# mcu.net
KiCad netlist of a schematic drawn in Altium Designer
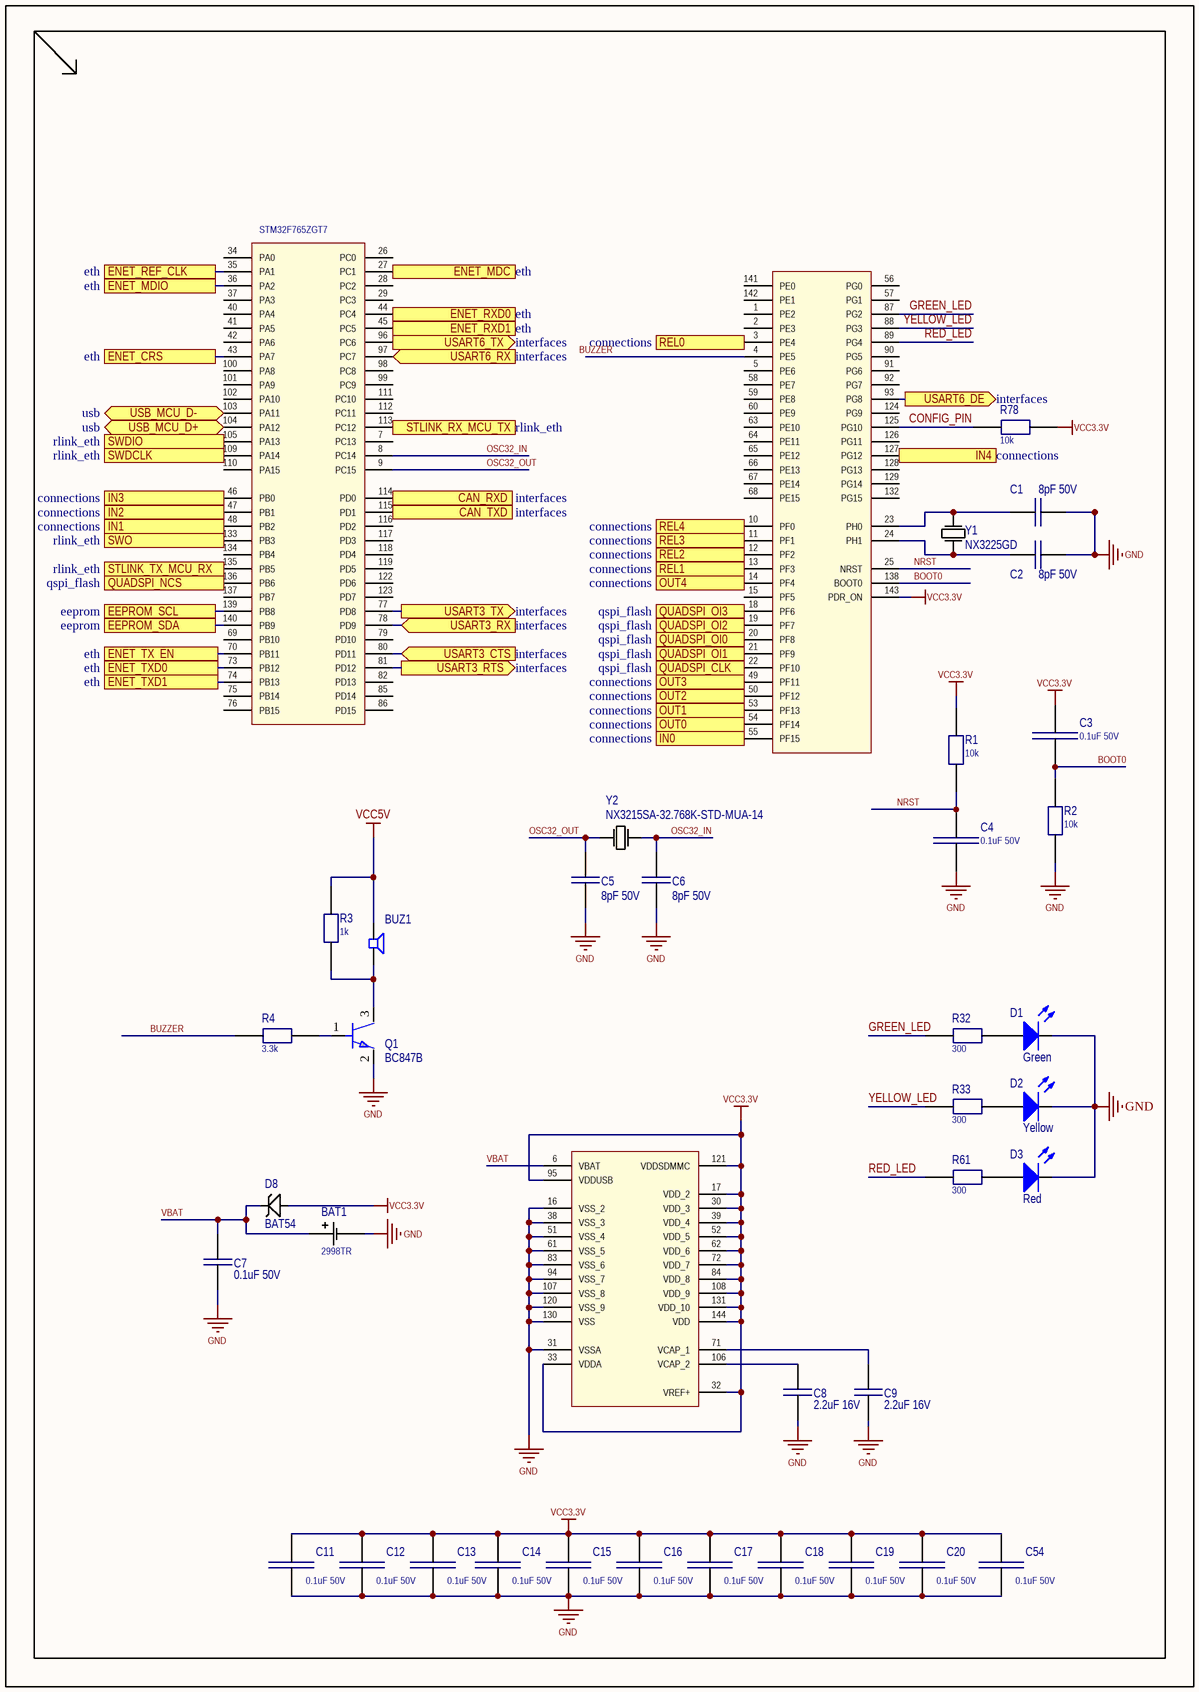
[diagram p0: mcu.SchDoc]

(export (version "E")
  (design (tool "Eeschema 10.0.6"))
  (components
    (comp (ref "BAT1")
      (value "2998TR")
      (footprint "BAT_2998TR")
      (description "Battery")
      (libsource (lib "battery_socets") (part "2998TR"))
    )
    (comp (ref "BUZ1")
      (value "~")
      (footprint "SPKR_PKMCS0909E4000-R1")
      (description "Piezoelectric Sounders")
      (fields (field (name "PART") "L-KLS3-SMT-09X1.8") (field (name "ALTERNATIVE PART") "PKMCS0909E4000-R1"))
      (libsource (lib "other") (part "BUZZER"))
    )
    (comp (ref "C1")
      (value "8pF 50V")
      (footprint "C_0603")
      (description "Capacitor")
      (fields (field (name "PART") "CC0603DRNPO9BN8R0"))
      (libsource (lib "capacitors") (part "CAP_SMD"))
    )
    (comp (ref "C2")
      (value "8pF 50V")
      (footprint "C_0603")
      (description "Capacitor")
      (fields (field (name "PART") "CC0603DRNPO9BN8R0"))
      (libsource (lib "capacitors") (part "CAP_SMD"))
    )
    (comp (ref "C3")
      (value "0.1uF 50V")
      (footprint "C_0603")
      (description "Capacitor")
      (fields (field (name "PART") "CC0603KPX7R9BB104"))
      (libsource (lib "AX_Altium_v2.3") (part "C0603"))
    )
    (comp (ref "C4")
      (value "0.1uF 50V")
      (footprint "C_0603")
      (description "Capacitor")
      (fields (field (name "PART") "CC0603KPX7R9BB104"))
      (libsource (lib "AX_Altium_v2.3") (part "C0603"))
    )
    (comp (ref "C5")
      (value "8pF 50V")
      (footprint "C_0603")
      (description "Capacitor")
      (fields (field (name "PART") "CC0603DRNPO9BN8R0"))
      (libsource (lib "capacitors") (part "CAP_SMD"))
    )
    (comp (ref "C6")
      (value "8pF 50V")
      (footprint "C_0603")
      (description "Capacitor")
      (fields (field (name "PART") "CC0603DRNPO9BN8R0"))
      (libsource (lib "capacitors") (part "CAP_SMD"))
    )
    (comp (ref "C7")
      (value "0.1uF 50V")
      (footprint "C_0603")
      (description "Capacitor")
      (fields (field (name "PART") "CC0603KPX7R9BB104"))
      (libsource (lib "capacitors") (part "CAP_SMD"))
    )
    (comp (ref "C8")
      (value "2.2uF 16V")
      (footprint "C_0603")
      (description "Capacitor")
      (fields (field (name "PART") "CC0603KRX5R7BB225"))
      (libsource (lib "capacitors") (part "CAP_SMD"))
    )
    (comp (ref "C9")
      (value "2.2uF 16V")
      (footprint "C_0603")
      (description "Capacitor")
      (fields (field (name "PART") "CC0603KRX5R7BB225"))
      (libsource (lib "capacitors") (part "CAP_SMD"))
    )
    (comp (ref "C11")
      (value "0.1uF 50V")
      (footprint "C_0603")
      (description "Capacitor")
      (fields (field (name "PART") "CC0603KPX7R9BB104"))
      (libsource (lib "AX_Altium_v2.3") (part "C0603"))
    )
    (comp (ref "C12")
      (value "0.1uF 50V")
      (footprint "C_0603")
      (description "Capacitor")
      (fields (field (name "PART") "CC0603KPX7R9BB104"))
      (libsource (lib "AX_Altium_v2.3") (part "C0603"))
    )
    (comp (ref "C13")
      (value "0.1uF 50V")
      (footprint "C_0603")
      (description "Capacitor")
      (fields (field (name "PART") "CC0603KPX7R9BB104"))
      (libsource (lib "AX_Altium_v2.3") (part "C0603"))
    )
    (comp (ref "C14")
      (value "0.1uF 50V")
      (footprint "C_0603")
      (description "Capacitor")
      (fields (field (name "PART") "CC0603KPX7R9BB104"))
      (libsource (lib "AX_Altium_v2.3") (part "C0603"))
    )
    (comp (ref "C15")
      (value "0.1uF 50V")
      (footprint "C_0603")
      (description "Capacitor")
      (fields (field (name "PART") "CC0603KPX7R9BB104"))
      (libsource (lib "AX_Altium_v2.3") (part "C0603"))
    )
    (comp (ref "C16")
      (value "0.1uF 50V")
      (footprint "C_0603")
      (description "Capacitor")
      (fields (field (name "PART") "CC0603KPX7R9BB104"))
      (libsource (lib "AX_Altium_v2.3") (part "C0603"))
    )
    (comp (ref "C17")
      (value "0.1uF 50V")
      (footprint "C_0603")
      (description "Capacitor")
      (fields (field (name "PART") "CC0603KPX7R9BB104"))
      (libsource (lib "AX_Altium_v2.3") (part "C0603"))
    )
    (comp (ref "C18")
      (value "0.1uF 50V")
      (footprint "C_0603")
      (description "Capacitor")
      (fields (field (name "PART") "CC0603KPX7R9BB104"))
      (libsource (lib "AX_Altium_v2.3") (part "C0603"))
    )
    (comp (ref "C19")
      (value "0.1uF 50V")
      (footprint "C_0603")
      (description "Capacitor")
      (fields (field (name "PART") "CC0603KPX7R9BB104"))
      (libsource (lib "AX_Altium_v2.3") (part "C0603"))
    )
    (comp (ref "C20")
      (value "0.1uF 50V")
      (footprint "C_0603")
      (description "Capacitor")
      (fields (field (name "PART") "CC0603KPX7R9BB104"))
      (libsource (lib "AX_Altium_v2.3") (part "C0603"))
    )
    (comp (ref "C54")
      (value "0.1uF 50V")
      (footprint "C_0603")
      (description "Capacitor")
      (fields (field (name "PART") "CC0603KPX7R9BB104"))
      (libsource (lib "AX_Altium_v2.3") (part "C0603"))
    )
    (comp (ref "D1")
      (value "Green")
      (footprint "LED_0603")
      (description "LED")
      (fields (field (name "PART") "FYLS-0603PGC") (field (name "ALTERNATIVE PART") "KP-1608CGCK"))
      (libsource (lib "led_lcd") (part "LED_SMT_0603"))
    )
    (comp (ref "D2")
      (value "Yellow")
      (footprint "LED_0603")
      (description "LED")
      (fields (field (name "PART") "FYLS-0603PGC") (field (name "ALTERNATIVE PART") "KP-1608CGCK"))
      (libsource (lib "led_lcd") (part "LED_SMT_0603"))
    )
    (comp (ref "D3")
      (value "Red")
      (footprint "LED_0603")
      (description "LED")
      (fields (field (name "PART") "FYLS-0603PGC") (field (name "ALTERNATIVE PART") "KP-1608CGCK"))
      (libsource (lib "led_lcd") (part "LED_SMT_0603"))
    )
    (comp (ref "D8")
      (value "BAT54")
      (footprint "SOT23")
      (description "Diode")
      (libsource (lib "diode") (part "BAT54"))
    )
    (comp (ref "Q1")
      (value "BC847B")
      (footprint "SOT23")
      (description "Transistor")
      (libsource (lib "AX_Altium_v2.3") (part "BC847B"))
    )
    (comp (ref "R1")
      (value "10k")
      (footprint "R_0603")
      (description "Resistor")
      (fields (field (name "PART") "RC0603FR-0710KL"))
      (libsource (lib "resistors") (part "RES_SMD"))
    )
    (comp (ref "R2")
      (value "10k")
      (footprint "R_0603")
      (description "Resistor")
      (fields (field (name "PART") "RC0603FR-0710KL"))
      (libsource (lib "resistors") (part "RES_SMD"))
    )
    (comp (ref "R3")
      (value "1k")
      (footprint "R_0603")
      (description "Resistor")
      (fields (field (name "PART") "RC0603FR-071KL"))
      (libsource (lib "resistors") (part "RES_SMD"))
    )
    (comp (ref "R4")
      (value "3.3k")
      (footprint "R_0603")
      (description "Resistor")
      (fields (field (name "PART") "RC0603FR-073K3L"))
      (libsource (lib "resistors") (part "RES_SMD"))
    )
    (comp (ref "R32")
      (value "300")
      (footprint "R_0603")
      (description "Resistor")
      (fields (field (name "PART") "RC0603FR-07300RL"))
      (libsource (lib "resistors") (part "R0603"))
    )
    (comp (ref "R33")
      (value "300")
      (footprint "R_0603")
      (description "Resistor")
      (fields (field (name "PART") "RC0603FR-07300RL"))
      (libsource (lib "resistors") (part "R0603"))
    )
    (comp (ref "R61")
      (value "300")
      (footprint "R_0603")
      (description "Resistor")
      (fields (field (name "PART") "RC0603FR-07300RL"))
      (libsource (lib "resistors") (part "R0603"))
    )
    (comp (ref "R78")
      (value "10k")
      (footprint "R_0603")
      (description "Resistor")
      (fields (field (name "PART") "RC0603FR-0710KL"))
      (libsource (lib "resistors") (part "RES_SMD"))
    )
    (comp (ref "U1")
      (value "STM32F765ZGT7")
      (footprint "TQFP144_M")
      (description "Microcontroller")
      (fields
        (field (name "MANUFACTURER_PART_NUMBER") "STM32F76XZXT")
        (field (name "PART") "STM32F765ZGT")
        (field (name "COPYRIGHT") "Copyright (C) 2016 Accelerated Designs. All rights reserved")
      )
      (libsource (lib "STM32 F4") (part "STM32F76XZXT"))
    )
    (comp (ref "Y1")
      (value "NX3225GD")
      (footprint "NX3225GD")
      (description "Crystal Oscillator")
      (fields (field (name "PART") "NX3225GD-8MHZ-STD-CRA-3"))
      (libsource (lib "crystals_oscillators") (part "NX3225GD"))
    )
    (comp (ref "Y2")
      (value "NX3215SA-32.768K-STD-MUA-14")
      (footprint "XTAL_NX3215SA-32.768K-STD-MUA-8")
      (description "Crystal Oscillator")
      (libsource (lib "crystals_oscillators") (part "NX3215SA-32.768K"))
    )
  )
  (nets
    (net (code "1") (name "/BOOT0") (class "Default")
      (node (ref "C3") (pin "2") (pinfunction "2_2") (pintype "passive"))
      (node (ref "R2") (pin "2") (pinfunction "2_2") (pintype "passive"))
      (node (ref "U1") (pin "138") (pinfunction "BOOT0_138") (pintype "passive"))
    )
    (net (code "2") (name "/BUZZER") (class "Default")
      (node (ref "R4") (pin "1") (pinfunction "1_1") (pintype "passive"))
      (node (ref "U1") (pin "4") (pinfunction "PE5_4") (pintype "passive"))
    )
    (net (code "3") (name "/CAN_RXD") (class "Default")
      (node (ref "U1") (pin "114") (pinfunction "PD0_114") (pintype "passive"))
    )
    (net (code "4") (name "/CAN_TXD") (class "Default")
      (node (ref "U1") (pin "115") (pinfunction "PD1_115") (pintype "passive"))
    )
    (net (code "5") (name "/CONFIG_PIN") (class "Default")
      (node (ref "R78") (pin "1") (pinfunction "1_1") (pintype "passive"))
      (node (ref "U1") (pin "125") (pinfunction "PG10_125") (pintype "passive"))
    )
    (net (code "6") (name "/EEPROM_SCL") (class "Default")
      (node (ref "U1") (pin "139") (pinfunction "PB8_139") (pintype "passive"))
    )
    (net (code "7") (name "/EEPROM_SDA") (class "Default")
      (node (ref "U1") (pin "140") (pinfunction "PB9_140") (pintype "passive"))
    )
    (net (code "8") (name "/ENET_CRS") (class "Default")
      (node (ref "U1") (pin "43") (pinfunction "PA7_43") (pintype "passive"))
    )
    (net (code "9") (name "/ENET_MDC") (class "Default")
      (node (ref "U1") (pin "27") (pinfunction "PC1_27") (pintype "passive"))
    )
    (net (code "10") (name "/ENET_MDIO") (class "Default")
      (node (ref "U1") (pin "36") (pinfunction "PA2_36") (pintype "passive"))
    )
    (net (code "11") (name "/ENET_REF_CLK") (class "Default")
      (node (ref "U1") (pin "35") (pinfunction "PA1_35") (pintype "passive"))
    )
    (net (code "12") (name "/ENET_RXD0") (class "Default")
      (node (ref "U1") (pin "44") (pinfunction "PC4_44") (pintype "passive"))
    )
    (net (code "13") (name "/ENET_RXD1") (class "Default")
      (node (ref "U1") (pin "45") (pinfunction "PC5_45") (pintype "passive"))
    )
    (net (code "14") (name "/ENET_TXD0") (class "Default")
      (node (ref "U1") (pin "73") (pinfunction "PB12_73") (pintype "passive"))
    )
    (net (code "15") (name "/ENET_TXD1") (class "Default")
      (node (ref "U1") (pin "74") (pinfunction "PB13_74") (pintype "passive"))
    )
    (net (code "16") (name "/ENET_TX_EN") (class "Default")
      (node (ref "U1") (pin "70") (pinfunction "PB11_70") (pintype "passive"))
    )
    (net (code "17") (name "/GREEN_LED") (class "Default")
      (node (ref "R32") (pin "2") (pinfunction "2_2") (pintype "passive"))
      (node (ref "U1") (pin "87") (pinfunction "PG2_87") (pintype "passive"))
    )
    (net (code "18") (name "/IN0") (class "Default")
      (node (ref "U1") (pin "55") (pinfunction "PF15_55") (pintype "passive"))
    )
    (net (code "19") (name "/IN1") (class "Default")
      (node (ref "U1") (pin "48") (pinfunction "PB2_48") (pintype "passive"))
    )
    (net (code "20") (name "/IN2") (class "Default")
      (node (ref "U1") (pin "47") (pinfunction "PB1_47") (pintype "passive"))
    )
    (net (code "21") (name "/IN3") (class "Default")
      (node (ref "U1") (pin "46") (pinfunction "PB0_46") (pintype "passive"))
    )
    (net (code "22") (name "/IN4") (class "Default")
      (node (ref "U1") (pin "127") (pinfunction "PG12_127") (pintype "passive"))
    )
    (net (code "23") (name "/NRST") (class "Default")
      (node (ref "C4") (pin "2") (pinfunction "2_2") (pintype "passive"))
      (node (ref "R1") (pin "1") (pinfunction "1_1") (pintype "passive"))
      (node (ref "U1") (pin "25") (pinfunction "NRST_25") (pintype "passive"))
    )
    (net (code "24") (name "/OSC32_IN") (class "Default")
      (node (ref "C6") (pin "2") (pinfunction "2_2") (pintype "passive"))
      (node (ref "U1") (pin "8") (pinfunction "PC14_8") (pintype "passive"))
      (node (ref "Y2") (pin "2") (pinfunction "OSC2_2") (pintype "passive"))
    )
    (net (code "25") (name "/OSC32_OUT") (class "Default")
      (node (ref "C5") (pin "2") (pinfunction "2_2") (pintype "passive"))
      (node (ref "U1") (pin "9") (pinfunction "PC15_9") (pintype "passive"))
      (node (ref "Y2") (pin "1") (pinfunction "OSC1_1") (pintype "passive"))
    )
    (net (code "26") (name "/OUT0") (class "Default")
      (node (ref "U1") (pin "54") (pinfunction "PF14_54") (pintype "passive"))
    )
    (net (code "27") (name "/OUT1") (class "Default")
      (node (ref "U1") (pin "53") (pinfunction "PF13_53") (pintype "passive"))
    )
    (net (code "28") (name "/OUT2") (class "Default")
      (node (ref "U1") (pin "50") (pinfunction "PF12_50") (pintype "passive"))
    )
    (net (code "29") (name "/OUT3") (class "Default")
      (node (ref "U1") (pin "49") (pinfunction "PF11_49") (pintype "passive"))
    )
    (net (code "30") (name "/OUT4") (class "Default")
      (node (ref "U1") (pin "14") (pinfunction "PF4_14") (pintype "passive"))
    )
    (net (code "31") (name "/QUADSPI_CLK") (class "Default")
      (node (ref "U1") (pin "22") (pinfunction "PF10_22") (pintype "passive"))
    )
    (net (code "32") (name "/QUADSPI_NCS") (class "Default")
      (node (ref "U1") (pin "136") (pinfunction "PB6_136") (pintype "passive"))
    )
    (net (code "33") (name "/QUADSPI_OI0") (class "Default")
      (node (ref "U1") (pin "20") (pinfunction "PF8_20") (pintype "passive"))
    )
    (net (code "34") (name "/QUADSPI_OI1") (class "Default")
      (node (ref "U1") (pin "21") (pinfunction "PF9_21") (pintype "passive"))
    )
    (net (code "35") (name "/QUADSPI_OI2") (class "Default")
      (node (ref "U1") (pin "19") (pinfunction "PF7_19") (pintype "passive"))
    )
    (net (code "36") (name "/QUADSPI_OI3") (class "Default")
      (node (ref "U1") (pin "18") (pinfunction "PF6_18") (pintype "passive"))
    )
    (net (code "37") (name "/RED_LED") (class "Default")
      (node (ref "R61") (pin "2") (pinfunction "2_2") (pintype "passive"))
      (node (ref "U1") (pin "89") (pinfunction "PG4_89") (pintype "passive"))
    )
    (net (code "38") (name "/REL0") (class "Default")
      (node (ref "U1") (pin "3") (pinfunction "PE4_3") (pintype "passive"))
    )
    (net (code "39") (name "/REL1") (class "Default")
      (node (ref "U1") (pin "13") (pinfunction "PF3_13") (pintype "passive"))
    )
    (net (code "40") (name "/REL2") (class "Default")
      (node (ref "U1") (pin "12") (pinfunction "PF2_12") (pintype "passive"))
    )
    (net (code "41") (name "/REL3") (class "Default")
      (node (ref "U1") (pin "11") (pinfunction "PF1_11") (pintype "passive"))
    )
    (net (code "42") (name "/REL4") (class "Default")
      (node (ref "U1") (pin "10") (pinfunction "PF0_10") (pintype "passive"))
    )
    (net (code "43") (name "/STLINK_RX_MCU_TX") (class "Default")
      (node (ref "U1") (pin "113") (pinfunction "PC12_113") (pintype "passive"))
    )
    (net (code "44") (name "/STLINK_TX_MCU_RX") (class "Default")
      (node (ref "U1") (pin "135") (pinfunction "PB5_135") (pintype "passive"))
    )
    (net (code "45") (name "/SWDCLK") (class "Default")
      (node (ref "U1") (pin "109") (pinfunction "PA14_109") (pintype "passive"))
    )
    (net (code "46") (name "/SWDIO") (class "Default")
      (node (ref "U1") (pin "105") (pinfunction "PA13_105") (pintype "passive"))
    )
    (net (code "47") (name "/SWO") (class "Default")
      (node (ref "U1") (pin "133") (pinfunction "PB3_133") (pintype "passive"))
    )
    (net (code "48") (name "/USART3_CTS") (class "Default")
      (node (ref "U1") (pin "80") (pinfunction "PD11_80") (pintype "passive"))
    )
    (net (code "49") (name "/USART3_RTS") (class "Default")
      (node (ref "U1") (pin "81") (pinfunction "PD12_81") (pintype "passive"))
    )
    (net (code "50") (name "/USART3_RX") (class "Default")
      (node (ref "U1") (pin "78") (pinfunction "PD9_78") (pintype "passive"))
    )
    (net (code "51") (name "/USART3_TX") (class "Default")
      (node (ref "U1") (pin "77") (pinfunction "PD8_77") (pintype "passive"))
    )
    (net (code "52") (name "/USART6_DE") (class "Default")
      (node (ref "U1") (pin "93") (pinfunction "PG8_93") (pintype "passive"))
    )
    (net (code "53") (name "/USART6_RX") (class "Default")
      (node (ref "U1") (pin "97") (pinfunction "PC7_97") (pintype "passive"))
    )
    (net (code "54") (name "/USART6_TX") (class "Default")
      (node (ref "U1") (pin "96") (pinfunction "PC6_96") (pintype "passive"))
    )
    (net (code "55") (name "/USB_MCU_D+") (class "Default")
      (node (ref "U1") (pin "104") (pinfunction "PA12_104") (pintype "passive"))
    )
    (net (code "56") (name "/USB_MCU_D-") (class "Default")
      (node (ref "U1") (pin "103") (pinfunction "PA11_103") (pintype "passive"))
    )
    (net (code "57") (name "/VBAT") (class "Default")
      (node (ref "BAT1") (pin "P1") (pinfunction "+_P1") (pintype "passive"))
      (node (ref "C7") (pin "2") (pinfunction "2_2") (pintype "passive"))
      (node (ref "D8") (pin "3") (pinfunction "3_3") (pintype "passive"))
      (node (ref "U1") (pin "6") (pinfunction "VBAT_6") (pintype "passive"))
    )
    (net (code "58") (name "/YELLOW_LED") (class "Default")
      (node (ref "R33") (pin "2") (pinfunction "2_2") (pintype "passive"))
      (node (ref "U1") (pin "88") (pinfunction "PG3_88") (pintype "passive"))
    )
    (net (code "59") (name "GND") (class "Default")
      (node (ref "BAT1") (pin "N") (pinfunction "-_N") (pintype "passive"))
      (node (ref "C1") (pin "1") (pinfunction "1_1") (pintype "passive"))
      (node (ref "C11") (pin "1") (pinfunction "1_1") (pintype "passive"))
      (node (ref "C12") (pin "1") (pinfunction "1_1") (pintype "passive"))
      (node (ref "C13") (pin "1") (pinfunction "1_1") (pintype "passive"))
      (node (ref "C14") (pin "1") (pinfunction "1_1") (pintype "passive"))
      (node (ref "C15") (pin "1") (pinfunction "1_1") (pintype "passive"))
      (node (ref "C16") (pin "1") (pinfunction "1_1") (pintype "passive"))
      (node (ref "C17") (pin "1") (pinfunction "1_1") (pintype "passive"))
      (node (ref "C18") (pin "1") (pinfunction "1_1") (pintype "passive"))
      (node (ref "C19") (pin "1") (pinfunction "1_1") (pintype "passive"))
      (node (ref "C2") (pin "1") (pinfunction "1_1") (pintype "passive"))
      (node (ref "C20") (pin "1") (pinfunction "1_1") (pintype "passive"))
      (node (ref "C4") (pin "1") (pinfunction "1_1") (pintype "passive"))
      (node (ref "C5") (pin "1") (pinfunction "1_1") (pintype "passive"))
      (node (ref "C54") (pin "1") (pinfunction "1_1") (pintype "passive"))
      (node (ref "C6") (pin "1") (pinfunction "1_1") (pintype "passive"))
      (node (ref "C7") (pin "1") (pinfunction "1_1") (pintype "passive"))
      (node (ref "C8") (pin "1") (pinfunction "1_1") (pintype "passive"))
      (node (ref "C9") (pin "1") (pinfunction "1_1") (pintype "passive"))
      (node (ref "D1") (pin "2") (pinfunction "K_2") (pintype "passive"))
      (node (ref "D2") (pin "2") (pinfunction "K_2") (pintype "passive"))
      (node (ref "D3") (pin "2") (pinfunction "K_2") (pintype "passive"))
      (node (ref "Q1") (pin "2") (pintype "passive"))
      (node (ref "R2") (pin "1") (pinfunction "1_1") (pintype "passive"))
      (node (ref "U1") (pin "107") (pinfunction "VSS_8_107") (pintype "passive"))
      (node (ref "U1") (pin "120") (pinfunction "VSS_9_120") (pintype "passive"))
      (node (ref "U1") (pin "130") (pinfunction "VSS_130") (pintype "passive"))
      (node (ref "U1") (pin "16") (pinfunction "VSS_2_16") (pintype "passive"))
      (node (ref "U1") (pin "31") (pinfunction "VSSA_31") (pintype "passive"))
      (node (ref "U1") (pin "38") (pinfunction "VSS_3_38") (pintype "passive"))
      (node (ref "U1") (pin "51") (pinfunction "VSS_4_51") (pintype "passive"))
      (node (ref "U1") (pin "61") (pinfunction "VSS_5_61") (pintype "passive"))
      (node (ref "U1") (pin "83") (pinfunction "VSS_6_83") (pintype "passive"))
      (node (ref "U1") (pin "94") (pinfunction "VSS_7_94") (pintype "passive"))
    )
    (net (code "60") (name "Net-(BUZ1-Pad2)") (class "Default")
      (node (ref "BUZ1") (pin "2") (pinfunction "2_2") (pintype "passive"))
      (node (ref "Q1") (pin "3") (pintype "passive"))
      (node (ref "R3") (pin "1") (pinfunction "1_1") (pintype "passive"))
    )
    (net (code "61") (name "Net-(D1-A)") (class "Default")
      (node (ref "D1") (pin "1") (pinfunction "A_1") (pintype "passive"))
      (node (ref "R32") (pin "1") (pinfunction "1_1") (pintype "passive"))
    )
    (net (code "62") (name "Net-(D2-A)") (class "Default")
      (node (ref "D2") (pin "1") (pinfunction "A_1") (pintype "passive"))
      (node (ref "R33") (pin "1") (pinfunction "1_1") (pintype "passive"))
    )
    (net (code "63") (name "Net-(D3-A)") (class "Default")
      (node (ref "D3") (pin "1") (pinfunction "A_1") (pintype "passive"))
      (node (ref "R61") (pin "1") (pinfunction "1_1") (pintype "passive"))
    )
    (net (code "64") (name "Net-(Q1-Pad1)") (class "Default")
      (node (ref "Q1") (pin "1") (pintype "passive"))
      (node (ref "R4") (pin "2") (pinfunction "2_2") (pintype "passive"))
    )
    (net (code "65") (name "Net-(U1B-PH0)") (class "Default")
      (node (ref "C1") (pin "2") (pinfunction "2_2") (pintype "passive"))
      (node (ref "U1") (pin "23") (pinfunction "PH0_23") (pintype "passive"))
      (node (ref "Y1") (pin "2") (pinfunction "OSC2_2") (pintype "passive"))
    )
    (net (code "66") (name "Net-(U1B-PH1)") (class "Default")
      (node (ref "C2") (pin "2") (pinfunction "2_2") (pintype "passive"))
      (node (ref "U1") (pin "24") (pinfunction "PH1_24") (pintype "passive"))
      (node (ref "Y1") (pin "1") (pinfunction "OSC1_1") (pintype "passive"))
    )
    (net (code "67") (name "Net-(U1C-VCAP_1)") (class "Default")
      (node (ref "C9") (pin "2") (pinfunction "2_2") (pintype "passive"))
      (node (ref "U1") (pin "71") (pinfunction "VCAP_1_71") (pintype "passive"))
    )
    (net (code "68") (name "Net-(U1C-VCAP_2)") (class "Default")
      (node (ref "C8") (pin "2") (pinfunction "2_2") (pintype "passive"))
      (node (ref "U1") (pin "106") (pinfunction "VCAP_2_106") (pintype "passive"))
    )
    (net (code "69") (name "VCC3.3V") (class "Default")
      (node (ref "C11") (pin "2") (pinfunction "2_2") (pintype "passive"))
      (node (ref "C12") (pin "2") (pinfunction "2_2") (pintype "passive"))
      (node (ref "C13") (pin "2") (pinfunction "2_2") (pintype "passive"))
      (node (ref "C14") (pin "2") (pinfunction "2_2") (pintype "passive"))
      (node (ref "C15") (pin "2") (pinfunction "2_2") (pintype "passive"))
      (node (ref "C16") (pin "2") (pinfunction "2_2") (pintype "passive"))
      (node (ref "C17") (pin "2") (pinfunction "2_2") (pintype "passive"))
      (node (ref "C18") (pin "2") (pinfunction "2_2") (pintype "passive"))
      (node (ref "C19") (pin "2") (pinfunction "2_2") (pintype "passive"))
      (node (ref "C20") (pin "2") (pinfunction "2_2") (pintype "passive"))
      (node (ref "C3") (pin "1") (pinfunction "1_1") (pintype "passive"))
      (node (ref "C54") (pin "2") (pinfunction "2_2") (pintype "passive"))
      (node (ref "D8") (pin "1") (pinfunction "1_1") (pintype "passive"))
      (node (ref "R1") (pin "2") (pinfunction "2_2") (pintype "passive"))
      (node (ref "R78") (pin "2") (pinfunction "2_2") (pintype "passive"))
      (node (ref "U1") (pin "108") (pinfunction "VDD_9_108") (pintype "passive"))
      (node (ref "U1") (pin "121") (pinfunction "VDDSDMMC_121") (pintype "passive"))
      (node (ref "U1") (pin "131") (pinfunction "VDD_10_131") (pintype "passive"))
      (node (ref "U1") (pin "143") (pinfunction "PDR_ON_143") (pintype "passive"))
      (node (ref "U1") (pin "144") (pinfunction "VDD_144") (pintype "passive"))
      (node (ref "U1") (pin "17") (pinfunction "VDD_2_17") (pintype "passive"))
      (node (ref "U1") (pin "30") (pinfunction "VDD_3_30") (pintype "passive"))
      (node (ref "U1") (pin "32") (pinfunction "VREF+_32") (pintype "passive"))
      (node (ref "U1") (pin "33") (pinfunction "VDDA_33") (pintype "passive"))
      (node (ref "U1") (pin "39") (pinfunction "VDD_4_39") (pintype "passive"))
      (node (ref "U1") (pin "52") (pinfunction "VDD_5_52") (pintype "passive"))
      (node (ref "U1") (pin "62") (pinfunction "VDD_6_62") (pintype "passive"))
      (node (ref "U1") (pin "72") (pinfunction "VDD_7_72") (pintype "passive"))
      (node (ref "U1") (pin "84") (pinfunction "VDD_8_84") (pintype "passive"))
      (node (ref "U1") (pin "95") (pinfunction "VDDUSB_95") (pintype "passive"))
    )
    (net (code "70") (name "VCC5V") (class "Default")
      (node (ref "BUZ1") (pin "1") (pinfunction "1_1") (pintype "passive"))
      (node (ref "R3") (pin "2") (pinfunction "2_2") (pintype "passive"))
    )
    (net (code "71") (name "unconnected-(U1A-PA0-Pad34)") (class "Default")
      (node (ref "U1") (pin "34") (pinfunction "PA0_34") (pintype "passive"))
    )
    (net (code "72") (name "unconnected-(U1A-PA3-Pad37)") (class "Default")
      (node (ref "U1") (pin "37") (pinfunction "PA3_37") (pintype "passive"))
    )
    (net (code "73") (name "unconnected-(U1A-PA4-Pad40)") (class "Default")
      (node (ref "U1") (pin "40") (pinfunction "PA4_40") (pintype "passive"))
    )
    (net (code "74") (name "unconnected-(U1A-PA5-Pad41)") (class "Default")
      (node (ref "U1") (pin "41") (pinfunction "PA5_41") (pintype "passive"))
    )
    (net (code "75") (name "unconnected-(U1A-PA6-Pad42)") (class "Default")
      (node (ref "U1") (pin "42") (pinfunction "PA6_42") (pintype "passive"))
    )
    (net (code "76") (name "unconnected-(U1A-PA8-Pad100)") (class "Default")
      (node (ref "U1") (pin "100") (pinfunction "PA8_100") (pintype "passive"))
    )
    (net (code "77") (name "unconnected-(U1A-PA9-Pad101)") (class "Default")
      (node (ref "U1") (pin "101") (pinfunction "PA9_101") (pintype "passive"))
    )
    (net (code "78") (name "unconnected-(U1A-PA10-Pad102)") (class "Default")
      (node (ref "U1") (pin "102") (pinfunction "PA10_102") (pintype "passive"))
    )
    (net (code "79") (name "unconnected-(U1A-PA15-Pad110)") (class "Default")
      (node (ref "U1") (pin "110") (pinfunction "PA15_110") (pintype "passive"))
    )
    (net (code "80") (name "unconnected-(U1A-PB4-Pad134)") (class "Default")
      (node (ref "U1") (pin "134") (pinfunction "PB4_134") (pintype "passive"))
    )
    (net (code "81") (name "unconnected-(U1A-PB7-Pad137)") (class "Default")
      (node (ref "U1") (pin "137") (pinfunction "PB7_137") (pintype "passive"))
    )
    (net (code "82") (name "unconnected-(U1A-PB10-Pad69)") (class "Default")
      (node (ref "U1") (pin "69") (pinfunction "PB10_69") (pintype "passive"))
    )
    (net (code "83") (name "unconnected-(U1A-PB14-Pad75)") (class "Default")
      (node (ref "U1") (pin "75") (pinfunction "PB14_75") (pintype "passive"))
    )
    (net (code "84") (name "unconnected-(U1A-PB15-Pad76)") (class "Default")
      (node (ref "U1") (pin "76") (pinfunction "PB15_76") (pintype "passive"))
    )
    (net (code "85") (name "unconnected-(U1A-PC0-Pad26)") (class "Default")
      (node (ref "U1") (pin "26") (pinfunction "PC0_26") (pintype "passive"))
    )
    (net (code "86") (name "unconnected-(U1A-PC2-Pad28)") (class "Default")
      (node (ref "U1") (pin "28") (pinfunction "PC2_28") (pintype "passive"))
    )
    (net (code "87") (name "unconnected-(U1A-PC3-Pad29)") (class "Default")
      (node (ref "U1") (pin "29") (pinfunction "PC3_29") (pintype "passive"))
    )
    (net (code "88") (name "unconnected-(U1A-PC8-Pad98)") (class "Default")
      (node (ref "U1") (pin "98") (pinfunction "PC8_98") (pintype "passive"))
    )
    (net (code "89") (name "unconnected-(U1A-PC9-Pad99)") (class "Default")
      (node (ref "U1") (pin "99") (pinfunction "PC9_99") (pintype "passive"))
    )
    (net (code "90") (name "unconnected-(U1A-PC10-Pad111)") (class "Default")
      (node (ref "U1") (pin "111") (pinfunction "PC10_111") (pintype "passive"))
    )
    (net (code "91") (name "unconnected-(U1A-PC11-Pad112)") (class "Default")
      (node (ref "U1") (pin "112") (pinfunction "PC11_112") (pintype "passive"))
    )
    (net (code "92") (name "unconnected-(U1A-PC13-Pad7)") (class "Default")
      (node (ref "U1") (pin "7") (pinfunction "PC13_7") (pintype "passive"))
    )
    (net (code "93") (name "unconnected-(U1A-PD2-Pad116)") (class "Default")
      (node (ref "U1") (pin "116") (pinfunction "PD2_116") (pintype "passive"))
    )
    (net (code "94") (name "unconnected-(U1A-PD3-Pad117)") (class "Default")
      (node (ref "U1") (pin "117") (pinfunction "PD3_117") (pintype "passive"))
    )
    (net (code "95") (name "unconnected-(U1A-PD4-Pad118)") (class "Default")
      (node (ref "U1") (pin "118") (pinfunction "PD4_118") (pintype "passive"))
    )
    (net (code "96") (name "unconnected-(U1A-PD5-Pad119)") (class "Default")
      (node (ref "U1") (pin "119") (pinfunction "PD5_119") (pintype "passive"))
    )
    (net (code "97") (name "unconnected-(U1A-PD6-Pad122)") (class "Default")
      (node (ref "U1") (pin "122") (pinfunction "PD6_122") (pintype "passive"))
    )
    (net (code "98") (name "unconnected-(U1A-PD7-Pad123)") (class "Default")
      (node (ref "U1") (pin "123") (pinfunction "PD7_123") (pintype "passive"))
    )
    (net (code "99") (name "unconnected-(U1A-PD10-Pad79)") (class "Default")
      (node (ref "U1") (pin "79") (pinfunction "PD10_79") (pintype "passive"))
    )
    (net (code "100") (name "unconnected-(U1A-PD13-Pad82)") (class "Default")
      (node (ref "U1") (pin "82") (pinfunction "PD13_82") (pintype "passive"))
    )
    (net (code "101") (name "unconnected-(U1A-PD14-Pad85)") (class "Default")
      (node (ref "U1") (pin "85") (pinfunction "PD14_85") (pintype "passive"))
    )
    (net (code "102") (name "unconnected-(U1A-PD15-Pad86)") (class "Default")
      (node (ref "U1") (pin "86") (pinfunction "PD15_86") (pintype "passive"))
    )
    (net (code "103") (name "unconnected-(U1B-PE0-Pad141)") (class "Default")
      (node (ref "U1") (pin "141") (pinfunction "PE0_141") (pintype "passive"))
    )
    (net (code "104") (name "unconnected-(U1B-PE1-Pad142)") (class "Default")
      (node (ref "U1") (pin "142") (pinfunction "PE1_142") (pintype "passive"))
    )
    (net (code "105") (name "unconnected-(U1B-PE2-Pad1)") (class "Default")
      (node (ref "U1") (pin "1") (pinfunction "PE2_1") (pintype "passive"))
    )
    (net (code "106") (name "unconnected-(U1B-PE3-Pad2)") (class "Default")
      (node (ref "U1") (pin "2") (pinfunction "PE3_2") (pintype "passive"))
    )
    (net (code "107") (name "unconnected-(U1B-PE6-Pad5)") (class "Default")
      (node (ref "U1") (pin "5") (pinfunction "PE6_5") (pintype "passive"))
    )
    (net (code "108") (name "unconnected-(U1B-PE7-Pad58)") (class "Default")
      (node (ref "U1") (pin "58") (pinfunction "PE7_58") (pintype "passive"))
    )
    (net (code "109") (name "unconnected-(U1B-PE8-Pad59)") (class "Default")
      (node (ref "U1") (pin "59") (pinfunction "PE8_59") (pintype "passive"))
    )
    (net (code "110") (name "unconnected-(U1B-PE9-Pad60)") (class "Default")
      (node (ref "U1") (pin "60") (pinfunction "PE9_60") (pintype "passive"))
    )
    (net (code "111") (name "unconnected-(U1B-PE10-Pad63)") (class "Default")
      (node (ref "U1") (pin "63") (pinfunction "PE10_63") (pintype "passive"))
    )
    (net (code "112") (name "unconnected-(U1B-PE11-Pad64)") (class "Default")
      (node (ref "U1") (pin "64") (pinfunction "PE11_64") (pintype "passive"))
    )
    (net (code "113") (name "unconnected-(U1B-PE12-Pad65)") (class "Default")
      (node (ref "U1") (pin "65") (pinfunction "PE12_65") (pintype "passive"))
    )
    (net (code "114") (name "unconnected-(U1B-PE13-Pad66)") (class "Default")
      (node (ref "U1") (pin "66") (pinfunction "PE13_66") (pintype "passive"))
    )
    (net (code "115") (name "unconnected-(U1B-PE14-Pad67)") (class "Default")
      (node (ref "U1") (pin "67") (pinfunction "PE14_67") (pintype "passive"))
    )
    (net (code "116") (name "unconnected-(U1B-PE15-Pad68)") (class "Default")
      (node (ref "U1") (pin "68") (pinfunction "PE15_68") (pintype "passive"))
    )
    (net (code "117") (name "unconnected-(U1B-PF5-Pad15)") (class "Default")
      (node (ref "U1") (pin "15") (pinfunction "PF5_15") (pintype "passive"))
    )
    (net (code "118") (name "unconnected-(U1B-PG0-Pad56)") (class "Default")
      (node (ref "U1") (pin "56") (pinfunction "PG0_56") (pintype "passive"))
    )
    (net (code "119") (name "unconnected-(U1B-PG1-Pad57)") (class "Default")
      (node (ref "U1") (pin "57") (pinfunction "PG1_57") (pintype "passive"))
    )
    (net (code "120") (name "unconnected-(U1B-PG5-Pad90)") (class "Default")
      (node (ref "U1") (pin "90") (pinfunction "PG5_90") (pintype "passive"))
    )
    (net (code "121") (name "unconnected-(U1B-PG6-Pad91)") (class "Default")
      (node (ref "U1") (pin "91") (pinfunction "PG6_91") (pintype "passive"))
    )
    (net (code "122") (name "unconnected-(U1B-PG7-Pad92)") (class "Default")
      (node (ref "U1") (pin "92") (pinfunction "PG7_92") (pintype "passive"))
    )
    (net (code "123") (name "unconnected-(U1B-PG9-Pad124)") (class "Default")
      (node (ref "U1") (pin "124") (pinfunction "PG9_124") (pintype "passive"))
    )
    (net (code "124") (name "unconnected-(U1B-PG11-Pad126)") (class "Default")
      (node (ref "U1") (pin "126") (pinfunction "PG11_126") (pintype "passive"))
    )
    (net (code "125") (name "unconnected-(U1B-PG13-Pad128)") (class "Default")
      (node (ref "U1") (pin "128") (pinfunction "PG13_128") (pintype "passive"))
    )
    (net (code "126") (name "unconnected-(U1B-PG14-Pad129)") (class "Default")
      (node (ref "U1") (pin "129") (pinfunction "PG14_129") (pintype "passive"))
    )
    (net (code "127") (name "unconnected-(U1B-PG15-Pad132)") (class "Default")
      (node (ref "U1") (pin "132") (pinfunction "PG15_132") (pintype "passive"))
    )
  )
)
